# feedback.net
KiCad netlist of a schematic drawn in Altium Designer
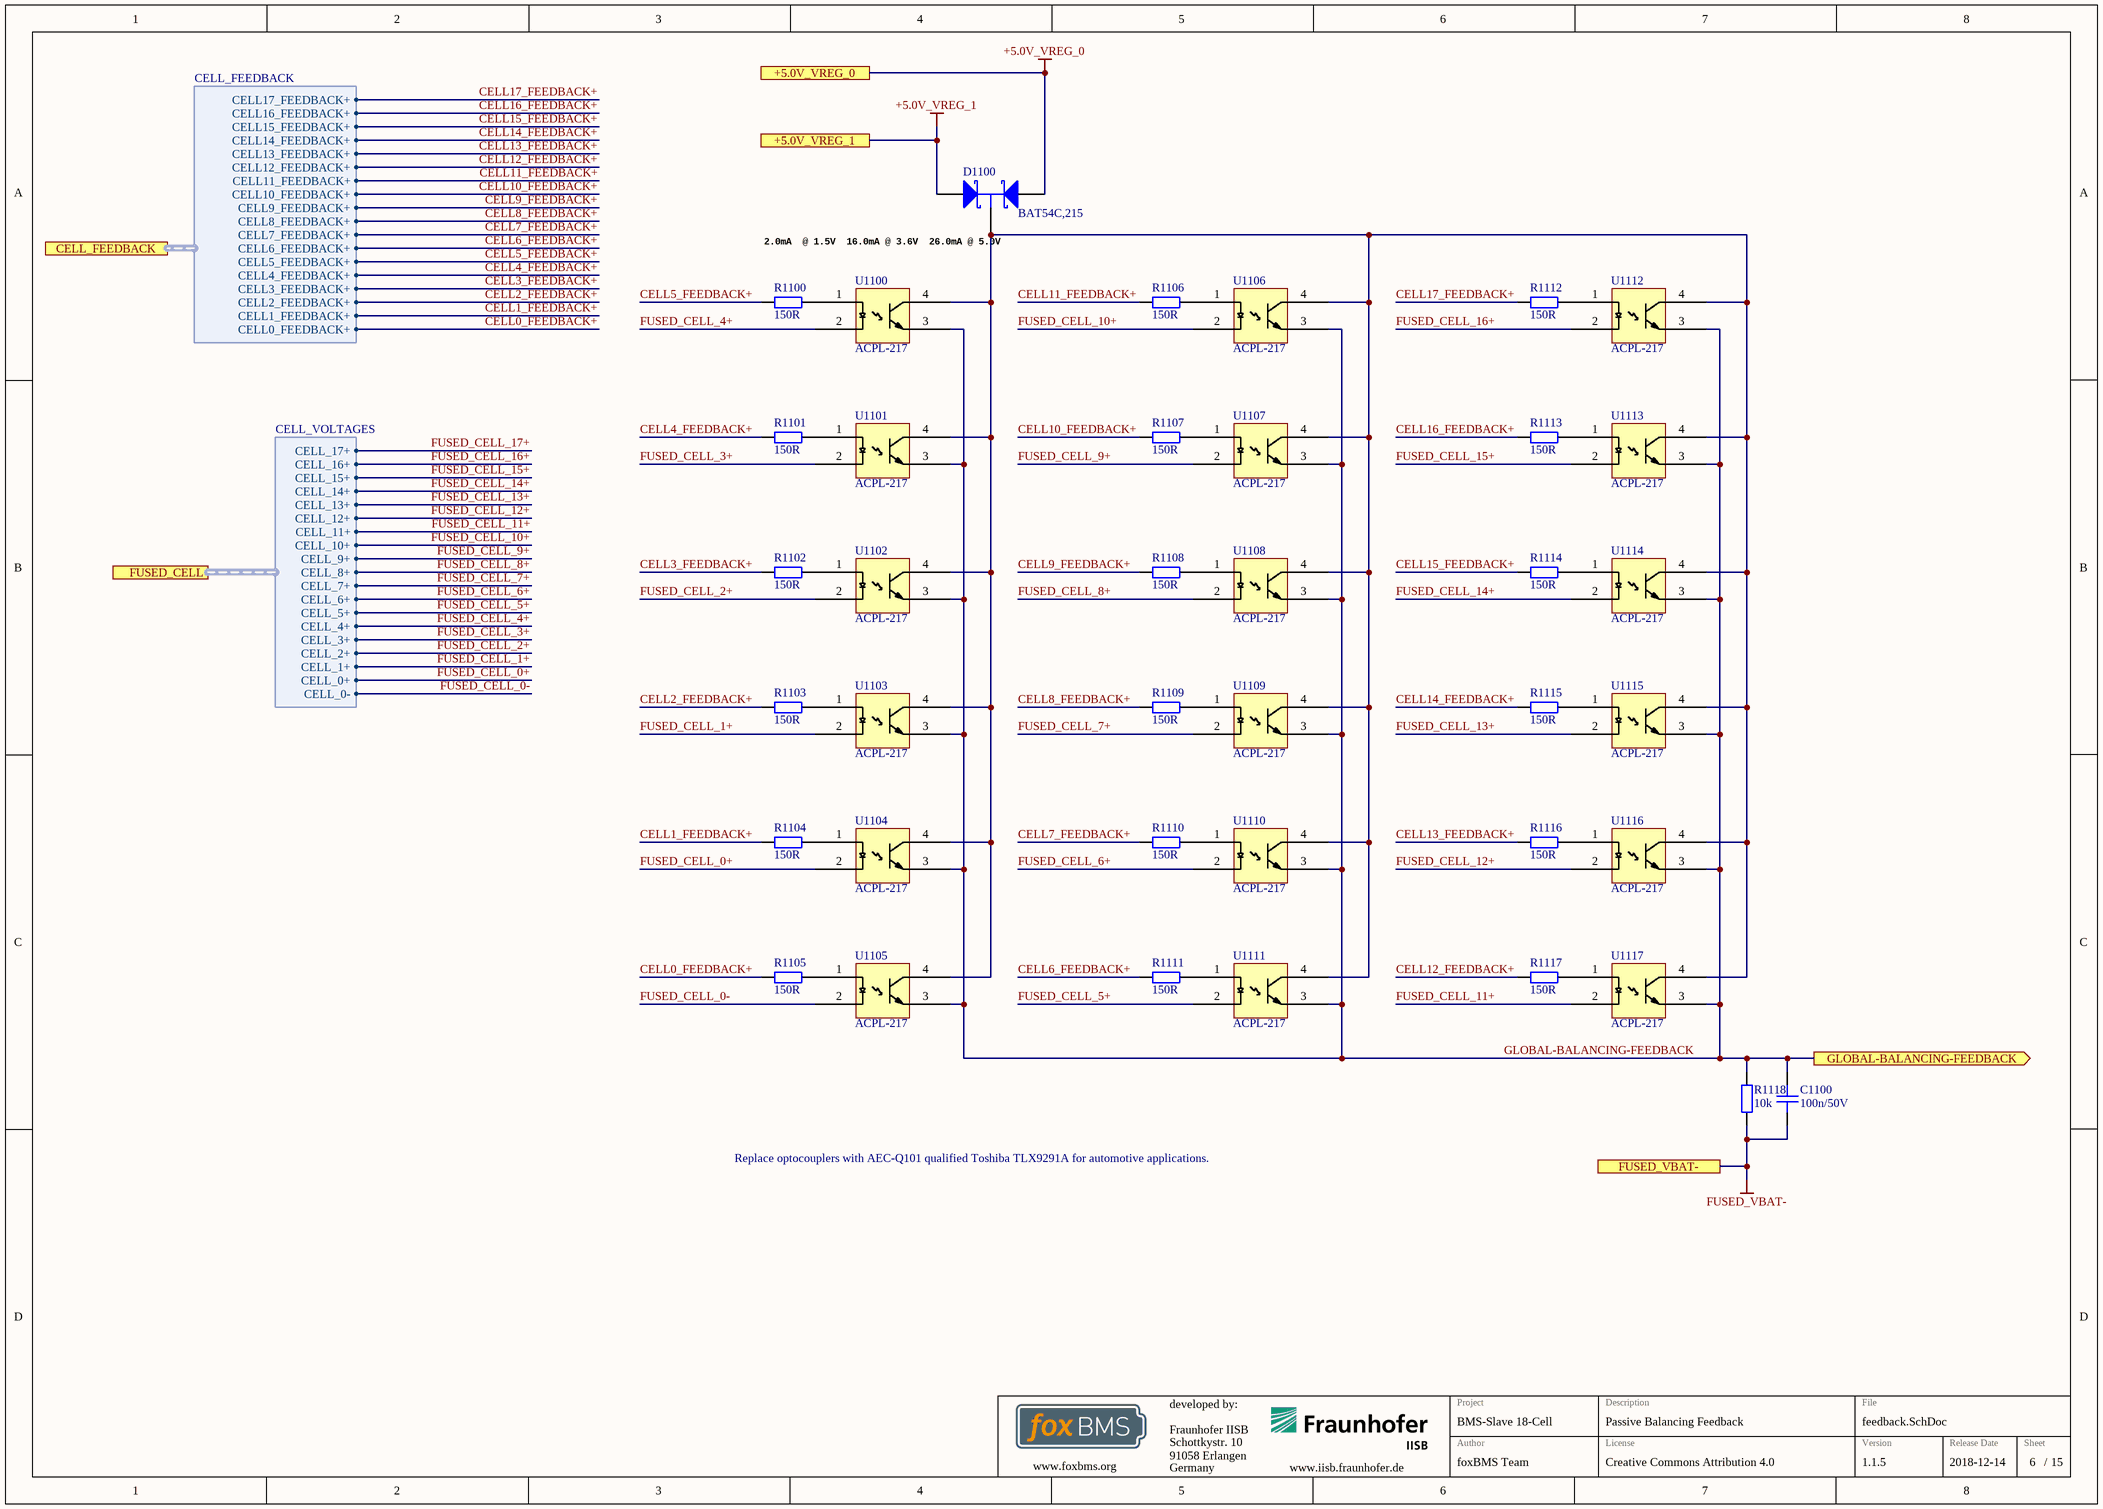
[diagram p0: feedback.SchDoc]

(export (version "E")
  (design (tool "Eeschema 10.0.6"))
  (components
    (comp (ref "C1100")
      (value "100n/50V")
      (footprint "CAPC1608X08N")
      (description "MLCC")
      (fields (field (name "PART NUMBER") "gen_C_ceramic_100n_50V_X7R_0603"))
      (libsource (lib "OE750") (part "C"))
    )
    (comp (ref "D1100")
      (value "BAT54C,215")
      (footprint "NXP-SOT23-3_V")
      (description "Schottky Barrier Diode, 30 V, 3-Pin SOT23, RoHS, Tape and Reel")
      (fields (field (name "MANUFACTURER") "NXP Semiconductors"))
      (libsource (lib "Altium Content Vault") (part "DSKY-AAK-3"))
    )
    (comp (ref "R1100")
      (value "150R")
      (footprint "RESC1608X05N")
      (description "SMD Resistor 150R 0603")
      (fields (field (name "PART NUMBER") "gen_R_150R_0603") (field (name "TOLERANCE") "1%"))
      (libsource (lib "OE750") (part "R"))
    )
    (comp (ref "R1101")
      (value "150R")
      (footprint "RESC1608X05N")
      (description "SMD Resistor 150R 0603")
      (fields (field (name "PART NUMBER") "gen_R_150R_0603") (field (name "TOLERANCE") "1%"))
      (libsource (lib "OE750") (part "R"))
    )
    (comp (ref "R1102")
      (value "150R")
      (footprint "RESC1608X05N")
      (description "SMD Resistor 150R 0603")
      (fields (field (name "PART NUMBER") "gen_R_150R_0603") (field (name "TOLERANCE") "1%"))
      (libsource (lib "OE750") (part "R"))
    )
    (comp (ref "R1103")
      (value "150R")
      (footprint "RESC1608X05N")
      (description "SMD Resistor 150R 0603")
      (fields (field (name "PART NUMBER") "gen_R_150R_0603") (field (name "TOLERANCE") "1%"))
      (libsource (lib "OE750") (part "R"))
    )
    (comp (ref "R1104")
      (value "150R")
      (footprint "RESC1608X05N")
      (description "SMD Resistor 150R 0603")
      (fields (field (name "PART NUMBER") "gen_R_150R_0603") (field (name "TOLERANCE") "1%"))
      (libsource (lib "OE750") (part "R"))
    )
    (comp (ref "R1105")
      (value "150R")
      (footprint "RESC1608X05N")
      (description "SMD Resistor 150R 0603")
      (fields (field (name "PART NUMBER") "gen_R_150R_0603") (field (name "TOLERANCE") "1%"))
      (libsource (lib "OE750") (part "R"))
    )
    (comp (ref "R1106")
      (value "150R")
      (footprint "RESC1608X05N")
      (description "SMD Resistor 150R 0603")
      (fields (field (name "PART NUMBER") "gen_R_150R_0603") (field (name "TOLERANCE") "1%"))
      (libsource (lib "OE750") (part "R"))
    )
    (comp (ref "R1107")
      (value "150R")
      (footprint "RESC1608X05N")
      (description "SMD Resistor 150R 0603")
      (fields (field (name "PART NUMBER") "gen_R_150R_0603") (field (name "TOLERANCE") "1%"))
      (libsource (lib "OE750") (part "R"))
    )
    (comp (ref "R1108")
      (value "150R")
      (footprint "RESC1608X05N")
      (description "SMD Resistor 150R 0603")
      (fields (field (name "PART NUMBER") "gen_R_150R_0603") (field (name "TOLERANCE") "1%"))
      (libsource (lib "OE750") (part "R"))
    )
    (comp (ref "R1109")
      (value "150R")
      (footprint "RESC1608X05N")
      (description "SMD Resistor 150R 0603")
      (fields (field (name "PART NUMBER") "gen_R_150R_0603") (field (name "TOLERANCE") "1%"))
      (libsource (lib "OE750") (part "R"))
    )
    (comp (ref "R1110")
      (value "150R")
      (footprint "RESC1608X05N")
      (description "SMD Resistor 150R 0603")
      (fields (field (name "PART NUMBER") "gen_R_150R_0603") (field (name "TOLERANCE") "1%"))
      (libsource (lib "OE750") (part "R"))
    )
    (comp (ref "R1111")
      (value "150R")
      (footprint "RESC1608X05N")
      (description "SMD Resistor 150R 0603")
      (fields (field (name "PART NUMBER") "gen_R_150R_0603") (field (name "TOLERANCE") "1%"))
      (libsource (lib "OE750") (part "R"))
    )
    (comp (ref "R1112")
      (value "150R")
      (footprint "RESC1608X05N")
      (description "SMD Resistor 150R 0603")
      (fields (field (name "PART NUMBER") "gen_R_150R_0603") (field (name "TOLERANCE") "1%"))
      (libsource (lib "OE750") (part "R"))
    )
    (comp (ref "R1113")
      (value "150R")
      (footprint "RESC1608X05N")
      (description "SMD Resistor 150R 0603")
      (fields (field (name "PART NUMBER") "gen_R_150R_0603") (field (name "TOLERANCE") "1%"))
      (libsource (lib "OE750") (part "R"))
    )
    (comp (ref "R1114")
      (value "150R")
      (footprint "RESC1608X05N")
      (description "SMD Resistor 150R 0603")
      (fields (field (name "PART NUMBER") "gen_R_150R_0603") (field (name "TOLERANCE") "1%"))
      (libsource (lib "OE750") (part "R"))
    )
    (comp (ref "R1115")
      (value "150R")
      (footprint "RESC1608X05N")
      (description "SMD Resistor 150R 0603")
      (fields (field (name "PART NUMBER") "gen_R_150R_0603") (field (name "TOLERANCE") "1%"))
      (libsource (lib "OE750") (part "R"))
    )
    (comp (ref "R1116")
      (value "150R")
      (footprint "RESC1608X05N")
      (description "SMD Resistor 150R 0603")
      (fields (field (name "PART NUMBER") "gen_R_150R_0603") (field (name "TOLERANCE") "1%"))
      (libsource (lib "OE750") (part "R"))
    )
    (comp (ref "R1117")
      (value "150R")
      (footprint "RESC1608X05N")
      (description "SMD Resistor 150R 0603")
      (fields (field (name "PART NUMBER") "gen_R_150R_0603") (field (name "TOLERANCE") "1%"))
      (libsource (lib "OE750") (part "R"))
    )
    (comp (ref "R1118")
      (value "10k")
      (footprint "RESC1608X05N")
      (description "SMD Resistor 10k 0603")
      (fields (field (name "PART NUMBER") "gen_R_10k_0603") (field (name "TOLERANCE") "1%"))
      (libsource (lib "OE750") (part "R"))
    )
    (comp (ref "U1100")
      (value "ACPL-217")
      (footprint "SOIC127P700X220-4N")
      (description "Optocoupler, Transistor Output, 1 Channel")
      (fields (field (name "PART NUMBER") "ACPL-217-56BE") (field (name "MANUFACTURER") "Broadcom Limited"))
      (libsource (lib "OE750") (part "ACPL-217"))
    )
    (comp (ref "U1101")
      (value "ACPL-217")
      (footprint "SOIC127P700X220-4N")
      (description "Optocoupler, Transistor Output, 1 Channel")
      (fields (field (name "PART NUMBER") "ACPL-217-56BE") (field (name "MANUFACTURER") "Broadcom Limited"))
      (libsource (lib "OE750") (part "ACPL-217"))
    )
    (comp (ref "U1102")
      (value "ACPL-217")
      (footprint "SOIC127P700X220-4N")
      (description "Optocoupler, Transistor Output, 1 Channel")
      (fields (field (name "PART NUMBER") "ACPL-217-56BE") (field (name "MANUFACTURER") "Broadcom Limited"))
      (libsource (lib "OE750") (part "ACPL-217"))
    )
    (comp (ref "U1103")
      (value "ACPL-217")
      (footprint "SOIC127P700X220-4N")
      (description "Optocoupler, Transistor Output, 1 Channel")
      (fields (field (name "PART NUMBER") "ACPL-217-56BE") (field (name "MANUFACTURER") "Broadcom Limited"))
      (libsource (lib "OE750") (part "ACPL-217"))
    )
    (comp (ref "U1104")
      (value "ACPL-217")
      (footprint "SOIC127P700X220-4N")
      (description "Optocoupler, Transistor Output, 1 Channel")
      (fields (field (name "PART NUMBER") "ACPL-217-56BE") (field (name "MANUFACTURER") "Broadcom Limited"))
      (libsource (lib "OE750") (part "ACPL-217"))
    )
    (comp (ref "U1105")
      (value "ACPL-217")
      (footprint "SOIC127P700X220-4N")
      (description "Optocoupler, Transistor Output, 1 Channel")
      (fields (field (name "PART NUMBER") "ACPL-217-56BE") (field (name "MANUFACTURER") "Broadcom Limited"))
      (libsource (lib "OE750") (part "ACPL-217"))
    )
    (comp (ref "U1106")
      (value "ACPL-217")
      (footprint "SOIC127P700X220-4N")
      (description "Optocoupler, Transistor Output, 1 Channel")
      (fields (field (name "PART NUMBER") "ACPL-217-56BE") (field (name "MANUFACTURER") "Broadcom Limited"))
      (libsource (lib "OE750") (part "ACPL-217"))
    )
    (comp (ref "U1107")
      (value "ACPL-217")
      (footprint "SOIC127P700X220-4N")
      (description "Optocoupler, Transistor Output, 1 Channel")
      (fields (field (name "PART NUMBER") "ACPL-217-56BE") (field (name "MANUFACTURER") "Broadcom Limited"))
      (libsource (lib "OE750") (part "ACPL-217"))
    )
    (comp (ref "U1108")
      (value "ACPL-217")
      (footprint "SOIC127P700X220-4N")
      (description "Optocoupler, Transistor Output, 1 Channel")
      (fields (field (name "PART NUMBER") "ACPL-217-56BE") (field (name "MANUFACTURER") "Broadcom Limited"))
      (libsource (lib "OE750") (part "ACPL-217"))
    )
    (comp (ref "U1109")
      (value "ACPL-217")
      (footprint "SOIC127P700X220-4N")
      (description "Optocoupler, Transistor Output, 1 Channel")
      (fields (field (name "PART NUMBER") "ACPL-217-56BE") (field (name "MANUFACTURER") "Broadcom Limited"))
      (libsource (lib "OE750") (part "ACPL-217"))
    )
    (comp (ref "U1110")
      (value "ACPL-217")
      (footprint "SOIC127P700X220-4N")
      (description "Optocoupler, Transistor Output, 1 Channel")
      (fields (field (name "PART NUMBER") "ACPL-217-56BE") (field (name "MANUFACTURER") "Broadcom Limited"))
      (libsource (lib "OE750") (part "ACPL-217"))
    )
    (comp (ref "U1111")
      (value "ACPL-217")
      (footprint "SOIC127P700X220-4N")
      (description "Optocoupler, Transistor Output, 1 Channel")
      (fields (field (name "PART NUMBER") "ACPL-217-56BE") (field (name "MANUFACTURER") "Broadcom Limited"))
      (libsource (lib "OE750") (part "ACPL-217"))
    )
    (comp (ref "U1112")
      (value "ACPL-217")
      (footprint "SOIC127P700X220-4N")
      (description "Optocoupler, Transistor Output, 1 Channel")
      (fields (field (name "PART NUMBER") "ACPL-217-56BE") (field (name "MANUFACTURER") "Broadcom Limited"))
      (libsource (lib "OE750") (part "ACPL-217"))
    )
    (comp (ref "U1113")
      (value "ACPL-217")
      (footprint "SOIC127P700X220-4N")
      (description "Optocoupler, Transistor Output, 1 Channel")
      (fields (field (name "PART NUMBER") "ACPL-217-56BE") (field (name "MANUFACTURER") "Broadcom Limited"))
      (libsource (lib "OE750") (part "ACPL-217"))
    )
    (comp (ref "U1114")
      (value "ACPL-217")
      (footprint "SOIC127P700X220-4N")
      (description "Optocoupler, Transistor Output, 1 Channel")
      (fields (field (name "PART NUMBER") "ACPL-217-56BE") (field (name "MANUFACTURER") "Broadcom Limited"))
      (libsource (lib "OE750") (part "ACPL-217"))
    )
    (comp (ref "U1115")
      (value "ACPL-217")
      (footprint "SOIC127P700X220-4N")
      (description "Optocoupler, Transistor Output, 1 Channel")
      (fields (field (name "PART NUMBER") "ACPL-217-56BE") (field (name "MANUFACTURER") "Broadcom Limited"))
      (libsource (lib "OE750") (part "ACPL-217"))
    )
    (comp (ref "U1116")
      (value "ACPL-217")
      (footprint "SOIC127P700X220-4N")
      (description "Optocoupler, Transistor Output, 1 Channel")
      (fields (field (name "PART NUMBER") "ACPL-217-56BE") (field (name "MANUFACTURER") "Broadcom Limited"))
      (libsource (lib "OE750") (part "ACPL-217"))
    )
    (comp (ref "U1117")
      (value "ACPL-217")
      (footprint "SOIC127P700X220-4N")
      (description "Optocoupler, Transistor Output, 1 Channel")
      (fields (field (name "PART NUMBER") "ACPL-217-56BE") (field (name "MANUFACTURER") "Broadcom Limited"))
      (libsource (lib "OE750") (part "ACPL-217"))
    )
  )
  (nets
    (net (code "3") (name "+5.0V_VREG_0") (class "Default")
      (node (ref "D1100") (pin "2") (pinfunction "A_2") (pintype "passive"))
    )
    (net (code "4") (name "+5.0V_VREG_1") (class "Default")
      (node (ref "D1100") (pin "1") (pinfunction "A_1") (pintype "passive"))
    )
    (net (code "5") (name "/CELL0_FEEDBACK+") (class "Default")
      (node (ref "R1105") (pin "1") (pinfunction "1_1") (pintype "passive"))
    )
    (net (code "6") (name "/CELL1_FEEDBACK+") (class "Default")
      (node (ref "R1104") (pin "1") (pinfunction "1_1") (pintype "passive"))
    )
    (net (code "7") (name "/CELL2_FEEDBACK+") (class "Default")
      (node (ref "R1103") (pin "1") (pinfunction "1_1") (pintype "passive"))
    )
    (net (code "8") (name "/CELL3_FEEDBACK+") (class "Default")
      (node (ref "R1102") (pin "1") (pinfunction "1_1") (pintype "passive"))
    )
    (net (code "9") (name "/CELL4_FEEDBACK+") (class "Default")
      (node (ref "R1101") (pin "1") (pinfunction "1_1") (pintype "passive"))
    )
    (net (code "10") (name "/CELL5_FEEDBACK+") (class "Default")
      (node (ref "R1100") (pin "1") (pinfunction "1_1") (pintype "passive"))
    )
    (net (code "11") (name "/CELL6_FEEDBACK+") (class "Default")
      (node (ref "R1111") (pin "1") (pinfunction "1_1") (pintype "passive"))
    )
    (net (code "12") (name "/CELL7_FEEDBACK+") (class "Default")
      (node (ref "R1110") (pin "1") (pinfunction "1_1") (pintype "passive"))
    )
    (net (code "13") (name "/CELL8_FEEDBACK+") (class "Default")
      (node (ref "R1109") (pin "1") (pinfunction "1_1") (pintype "passive"))
    )
    (net (code "14") (name "/CELL9_FEEDBACK+") (class "Default")
      (node (ref "R1108") (pin "1") (pinfunction "1_1") (pintype "passive"))
    )
    (net (code "15") (name "/CELL10_FEEDBACK+") (class "Default")
      (node (ref "R1107") (pin "1") (pinfunction "1_1") (pintype "passive"))
    )
    (net (code "16") (name "/CELL11_FEEDBACK+") (class "Default")
      (node (ref "R1106") (pin "1") (pinfunction "1_1") (pintype "passive"))
    )
    (net (code "17") (name "/CELL12_FEEDBACK+") (class "Default")
      (node (ref "R1117") (pin "1") (pinfunction "1_1") (pintype "passive"))
    )
    (net (code "18") (name "/CELL13_FEEDBACK+") (class "Default")
      (node (ref "R1116") (pin "1") (pinfunction "1_1") (pintype "passive"))
    )
    (net (code "19") (name "/CELL14_FEEDBACK+") (class "Default")
      (node (ref "R1115") (pin "1") (pinfunction "1_1") (pintype "passive"))
    )
    (net (code "20") (name "/CELL15_FEEDBACK+") (class "Default")
      (node (ref "R1114") (pin "1") (pinfunction "1_1") (pintype "passive"))
    )
    (net (code "21") (name "/CELL16_FEEDBACK+") (class "Default")
      (node (ref "R1113") (pin "1") (pinfunction "1_1") (pintype "passive"))
    )
    (net (code "22") (name "/CELL17_FEEDBACK+") (class "Default")
      (node (ref "R1112") (pin "1") (pinfunction "1_1") (pintype "passive"))
    )
    (net (code "23") (name "/FUSED_CELL_0+") (class "Default")
      (node (ref "U1104") (pin "2") (pintype "power_in"))
    )
    (net (code "24") (name "/FUSED_CELL_0-") (class "Default")
      (node (ref "U1105") (pin "2") (pintype "power_in"))
    )
    (net (code "25") (name "/FUSED_CELL_1+") (class "Default")
      (node (ref "U1103") (pin "2") (pintype "power_in"))
    )
    (net (code "26") (name "/FUSED_CELL_2+") (class "Default")
      (node (ref "U1102") (pin "2") (pintype "power_in"))
    )
    (net (code "27") (name "/FUSED_CELL_3+") (class "Default")
      (node (ref "U1101") (pin "2") (pintype "power_in"))
    )
    (net (code "28") (name "/FUSED_CELL_4+") (class "Default")
      (node (ref "U1100") (pin "2") (pintype "power_in"))
    )
    (net (code "29") (name "/FUSED_CELL_5+") (class "Default")
      (node (ref "U1111") (pin "2") (pintype "power_in"))
    )
    (net (code "30") (name "/FUSED_CELL_6+") (class "Default")
      (node (ref "U1110") (pin "2") (pintype "power_in"))
    )
    (net (code "31") (name "/FUSED_CELL_7+") (class "Default")
      (node (ref "U1109") (pin "2") (pintype "power_in"))
    )
    (net (code "32") (name "/FUSED_CELL_8+") (class "Default")
      (node (ref "U1108") (pin "2") (pintype "power_in"))
    )
    (net (code "33") (name "/FUSED_CELL_9+") (class "Default")
      (node (ref "U1107") (pin "2") (pintype "power_in"))
    )
    (net (code "34") (name "/FUSED_CELL_10+") (class "Default")
      (node (ref "U1106") (pin "2") (pintype "power_in"))
    )
    (net (code "35") (name "/FUSED_CELL_11+") (class "Default")
      (node (ref "U1117") (pin "2") (pintype "power_in"))
    )
    (net (code "36") (name "/FUSED_CELL_12+") (class "Default")
      (node (ref "U1116") (pin "2") (pintype "power_in"))
    )
    (net (code "37") (name "/FUSED_CELL_13+") (class "Default")
      (node (ref "U1115") (pin "2") (pintype "power_in"))
    )
    (net (code "38") (name "/FUSED_CELL_14+") (class "Default")
      (node (ref "U1114") (pin "2") (pintype "power_in"))
    )
    (net (code "39") (name "/FUSED_CELL_15+") (class "Default")
      (node (ref "U1113") (pin "2") (pintype "power_in"))
    )
    (net (code "40") (name "/FUSED_CELL_16+") (class "Default")
      (node (ref "U1112") (pin "2") (pintype "power_in"))
    )
    (net (code "42") (name "/GLOBAL-BALANCING-FEEDBACK") (class "Default")
      (node (ref "C1100") (pin "2") (pinfunction "2_2") (pintype "passive"))
      (node (ref "R1118") (pin "1") (pinfunction "1_1") (pintype "passive"))
      (node (ref "U1100") (pin "3") (pintype "passive"))
      (node (ref "U1101") (pin "3") (pintype "passive"))
      (node (ref "U1102") (pin "3") (pintype "passive"))
      (node (ref "U1103") (pin "3") (pintype "passive"))
      (node (ref "U1104") (pin "3") (pintype "passive"))
      (node (ref "U1105") (pin "3") (pintype "passive"))
      (node (ref "U1106") (pin "3") (pintype "passive"))
      (node (ref "U1107") (pin "3") (pintype "passive"))
      (node (ref "U1108") (pin "3") (pintype "passive"))
      (node (ref "U1109") (pin "3") (pintype "passive"))
      (node (ref "U1110") (pin "3") (pintype "passive"))
      (node (ref "U1111") (pin "3") (pintype "passive"))
      (node (ref "U1112") (pin "3") (pintype "passive"))
      (node (ref "U1113") (pin "3") (pintype "passive"))
      (node (ref "U1114") (pin "3") (pintype "passive"))
      (node (ref "U1115") (pin "3") (pintype "passive"))
      (node (ref "U1116") (pin "3") (pintype "passive"))
      (node (ref "U1117") (pin "3") (pintype "passive"))
    )
    (net (code "45") (name "FUSED_VBAT-") (class "Default")
      (node (ref "C1100") (pin "1") (pinfunction "1_1") (pintype "passive"))
      (node (ref "R1118") (pin "2") (pinfunction "2_2") (pintype "passive"))
    )
    (net (code "46") (name "Net-(D1100-K)") (class "Default")
      (node (ref "D1100") (pin "3") (pinfunction "K_3") (pintype "passive"))
      (node (ref "U1100") (pin "4") (pintype "passive"))
      (node (ref "U1101") (pin "4") (pintype "passive"))
      (node (ref "U1102") (pin "4") (pintype "passive"))
      (node (ref "U1103") (pin "4") (pintype "passive"))
      (node (ref "U1104") (pin "4") (pintype "passive"))
      (node (ref "U1105") (pin "4") (pintype "passive"))
      (node (ref "U1106") (pin "4") (pintype "passive"))
      (node (ref "U1107") (pin "4") (pintype "passive"))
      (node (ref "U1108") (pin "4") (pintype "passive"))
      (node (ref "U1109") (pin "4") (pintype "passive"))
      (node (ref "U1110") (pin "4") (pintype "passive"))
      (node (ref "U1111") (pin "4") (pintype "passive"))
      (node (ref "U1112") (pin "4") (pintype "passive"))
      (node (ref "U1113") (pin "4") (pintype "passive"))
      (node (ref "U1114") (pin "4") (pintype "passive"))
      (node (ref "U1115") (pin "4") (pintype "passive"))
      (node (ref "U1116") (pin "4") (pintype "passive"))
      (node (ref "U1117") (pin "4") (pintype "passive"))
    )
    (net (code "47") (name "Net-(R1100-Pad2)") (class "Default")
      (node (ref "R1100") (pin "2") (pinfunction "2_2") (pintype "passive"))
      (node (ref "U1100") (pin "1") (pintype "passive"))
    )
    (net (code "48") (name "Net-(R1101-Pad2)") (class "Default")
      (node (ref "R1101") (pin "2") (pinfunction "2_2") (pintype "passive"))
      (node (ref "U1101") (pin "1") (pintype "passive"))
    )
    (net (code "49") (name "Net-(R1102-Pad2)") (class "Default")
      (node (ref "R1102") (pin "2") (pinfunction "2_2") (pintype "passive"))
      (node (ref "U1102") (pin "1") (pintype "passive"))
    )
    (net (code "50") (name "Net-(R1103-Pad2)") (class "Default")
      (node (ref "R1103") (pin "2") (pinfunction "2_2") (pintype "passive"))
      (node (ref "U1103") (pin "1") (pintype "passive"))
    )
    (net (code "51") (name "Net-(R1104-Pad2)") (class "Default")
      (node (ref "R1104") (pin "2") (pinfunction "2_2") (pintype "passive"))
      (node (ref "U1104") (pin "1") (pintype "passive"))
    )
    (net (code "52") (name "Net-(R1105-Pad2)") (class "Default")
      (node (ref "R1105") (pin "2") (pinfunction "2_2") (pintype "passive"))
      (node (ref "U1105") (pin "1") (pintype "passive"))
    )
    (net (code "53") (name "Net-(R1106-Pad2)") (class "Default")
      (node (ref "R1106") (pin "2") (pinfunction "2_2") (pintype "passive"))
      (node (ref "U1106") (pin "1") (pintype "passive"))
    )
    (net (code "54") (name "Net-(R1107-Pad2)") (class "Default")
      (node (ref "R1107") (pin "2") (pinfunction "2_2") (pintype "passive"))
      (node (ref "U1107") (pin "1") (pintype "passive"))
    )
    (net (code "55") (name "Net-(R1108-Pad2)") (class "Default")
      (node (ref "R1108") (pin "2") (pinfunction "2_2") (pintype "passive"))
      (node (ref "U1108") (pin "1") (pintype "passive"))
    )
    (net (code "56") (name "Net-(R1109-Pad2)") (class "Default")
      (node (ref "R1109") (pin "2") (pinfunction "2_2") (pintype "passive"))
      (node (ref "U1109") (pin "1") (pintype "passive"))
    )
    (net (code "57") (name "Net-(R1110-Pad2)") (class "Default")
      (node (ref "R1110") (pin "2") (pinfunction "2_2") (pintype "passive"))
      (node (ref "U1110") (pin "1") (pintype "passive"))
    )
    (net (code "58") (name "Net-(R1111-Pad2)") (class "Default")
      (node (ref "R1111") (pin "2") (pinfunction "2_2") (pintype "passive"))
      (node (ref "U1111") (pin "1") (pintype "passive"))
    )
    (net (code "59") (name "Net-(R1112-Pad2)") (class "Default")
      (node (ref "R1112") (pin "2") (pinfunction "2_2") (pintype "passive"))
      (node (ref "U1112") (pin "1") (pintype "passive"))
    )
    (net (code "60") (name "Net-(R1113-Pad2)") (class "Default")
      (node (ref "R1113") (pin "2") (pinfunction "2_2") (pintype "passive"))
      (node (ref "U1113") (pin "1") (pintype "passive"))
    )
    (net (code "61") (name "Net-(R1114-Pad2)") (class "Default")
      (node (ref "R1114") (pin "2") (pinfunction "2_2") (pintype "passive"))
      (node (ref "U1114") (pin "1") (pintype "passive"))
    )
    (net (code "62") (name "Net-(R1115-Pad2)") (class "Default")
      (node (ref "R1115") (pin "2") (pinfunction "2_2") (pintype "passive"))
      (node (ref "U1115") (pin "1") (pintype "passive"))
    )
    (net (code "63") (name "Net-(R1116-Pad2)") (class "Default")
      (node (ref "R1116") (pin "2") (pinfunction "2_2") (pintype "passive"))
      (node (ref "U1116") (pin "1") (pintype "passive"))
    )
    (net (code "64") (name "Net-(R1117-Pad2)") (class "Default")
      (node (ref "R1117") (pin "2") (pinfunction "2_2") (pintype "passive"))
      (node (ref "U1117") (pin "1") (pintype "passive"))
    )
  )
)
